# Charger.net
KiCad netlist of a schematic drawn in Altium Designer
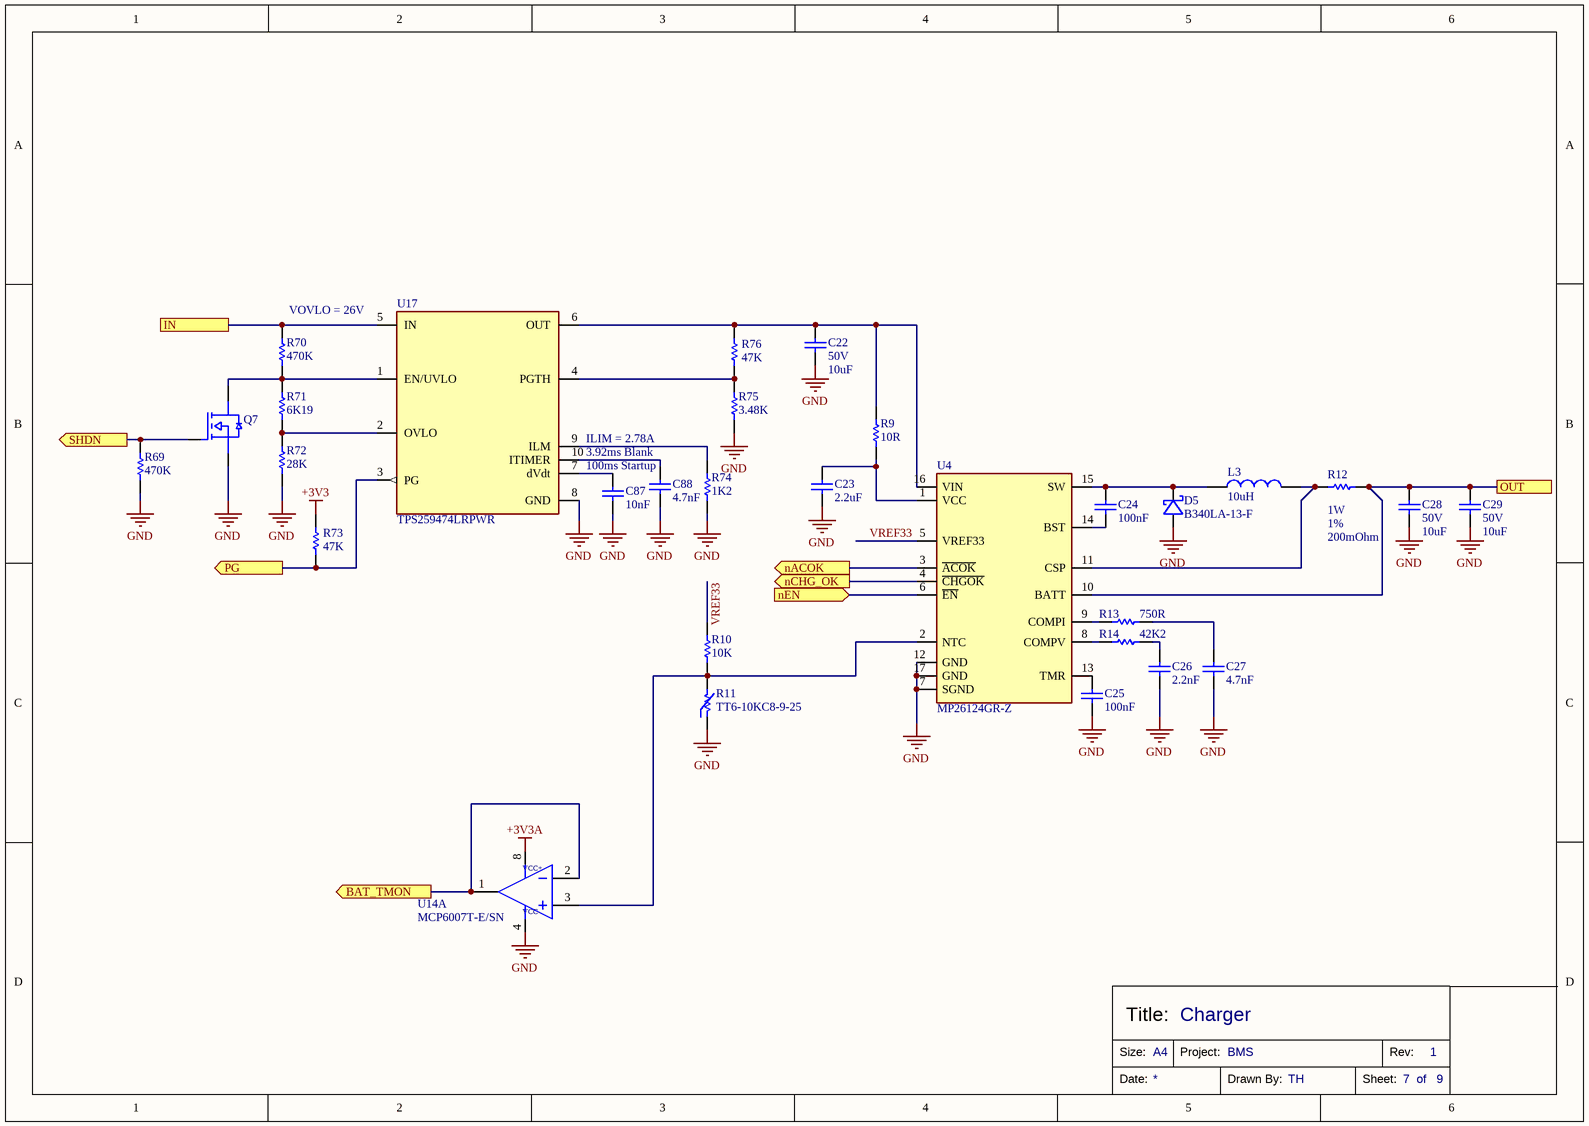
[diagram p0: Charger.SchDoc]

(export (version "E")
  (design (tool "Eeschema 10.0.6"))
  (components
    (comp (ref "C22")
      (value "CL32B106KBJNNNE")
      (footprint "CAPC1210X090")
      (description "10 µF ±10% 50V Ceramic Capacitor X7R 1210 (3225 Metric)")
      (fields
        (field (name "DISTRIBUTOR PART NUMBER") "1276-3387-1-ND")
        (field (name "TOLERANCE") "10%")
        (field (name "VOLTAGE RATING") "50V")
        (field (name "CAPACITANCE") "10uF")
      )
      (libsource (lib "Ahristi_Library") (part "CL32B106KBJNNNE"))
    )
    (comp (ref "C23")
      (value "CL21A225KBFNNNE")
      (footprint "CAPC0805X060")
      (description "2.2uF ±10% 25V Ceramic Capacitor X7R 0805 (2012 Metric)")
      (fields
        (field (name "DISTRIBUTOR PART NUMBER") "1276-6702-1-ND")
        (field (name "TOLERANCE") "10%")
        (field (name "CAPACITANCE") "2.2uF")
      )
      (libsource (lib "Ahristi_Library") (part "CL21A225KBFNNNE"))
    )
    (comp (ref "C24")
      (value "C0603C104K5RACTU")
      (footprint "CAPC0603X040")
      (description "0.1 µF ±10% 50V Ceramic Capacitor X7R 0603 (1608 Metric)")
      (fields
        (field (name "DISTRIBUTOR PART NUMBER") "399-C0603C104K5RACTUCT-ND")
        (field (name "TOLERANCE") "10%")
        (field (name "CAPACITANCE") "100nF")
      )
      (libsource (lib "Ahristi_Library") (part "C0603C104K5RACTU"))
    )
    (comp (ref "C25")
      (value "C0603C104K5RACTU")
      (footprint "CAPC0603X040")
      (description "0.1 µF ±10% 50V Ceramic Capacitor X7R 0603 (1608 Metric)")
      (fields
        (field (name "DISTRIBUTOR PART NUMBER") "399-C0603C104K5RACTUCT-ND")
        (field (name "TOLERANCE") "10%")
        (field (name "CAPACITANCE") "100nF")
      )
      (libsource (lib "Ahristi_Library") (part "C0603C104K5RACTU"))
    )
    (comp (ref "C26")
      (value "CL10B222KB8WPNC")
      (footprint "CAPC0603X060")
      (description "2.2nF ±10% 50V Ceramic Capacitor X7R 0603 (1608 Metric)")
      (fields
        (field (name "DISTRIBUTOR PART NUMBER") "1276-6530-1-ND")
        (field (name "TOLERANCE") "10%")
        (field (name "CAPACITANCE") "2.2nF")
      )
      (libsource (lib "Ahristi_Library") (part "CL10B222KB8WPNC"))
    )
    (comp (ref "C27")
      (value "C0603C472K4RECAUTO")
      (footprint "CAPC0603X040")
      (description "4.7nF ±10% 16V Ceramic Capacitor X7R 0603 (1608 Metric)")
      (fields
        (field (name "TOLERANCE") "10%")
        (field (name "DISTRIBUTOR PART NUMBER") "399-17879-1-ND")
        (field (name "CAPACITANCE") "4.7nF")
      )
      (libsource (lib "Ahristi_Library") (part "C0603C472K4RECAUTO"))
    )
    (comp (ref "C28")
      (value "CL32B106KBJNNNE")
      (footprint "CAPC1210X090")
      (description "10 µF ±10% 50V Ceramic Capacitor X7R 1210 (3225 Metric)")
      (fields
        (field (name "DISTRIBUTOR PART NUMBER") "1276-3387-1-ND")
        (field (name "TOLERANCE") "10%")
        (field (name "VOLTAGE RATING") "50V")
        (field (name "CAPACITANCE") "10uF")
      )
      (libsource (lib "Ahristi_Library") (part "CL32B106KBJNNNE"))
    )
    (comp (ref "C29")
      (value "CL32B106KBJNNNE")
      (footprint "CAPC1210X090")
      (description "10 µF ±10% 50V Ceramic Capacitor X7R 1210 (3225 Metric)")
      (fields
        (field (name "DISTRIBUTOR PART NUMBER") "1276-3387-1-ND")
        (field (name "TOLERANCE") "10%")
        (field (name "VOLTAGE RATING") "50V")
        (field (name "CAPACITANCE") "10uF")
      )
      (libsource (lib "Ahristi_Library") (part "CL32B106KBJNNNE"))
    )
    (comp (ref "C87")
      (value "CL10B103KB8NNNC")
      (footprint "CAPC0603X060")
      (description "10nF ±10% 50V Ceramic Capacitor X7R 0603 (1608 Metric)")
      (fields
        (field (name "DISTRIBUTOR PART NUMBER") "1276-1009-1-ND")
        (field (name "TOLERANCE") "10%")
        (field (name "CAPACITANCE") "10nF")
      )
      (libsource (lib "Ahristi_Library") (part "CL10B103KB8NNNC"))
    )
    (comp (ref "C88")
      (value "C0603C472K4RECAUTO")
      (footprint "CAPC0603X040")
      (description "4.7nF ±10% 16V Ceramic Capacitor X7R 0603 (1608 Metric)")
      (fields
        (field (name "TOLERANCE") "10%")
        (field (name "DISTRIBUTOR PART NUMBER") "399-17879-1-ND")
        (field (name "CAPACITANCE") "4.7nF")
      )
      (libsource (lib "Ahristi_Library") (part "C0603C472K4RECAUTO"))
    )
    (comp (ref "D5")
      (value "B340LA-13-F")
      (footprint "DO-214")
      (description "Diode Schottky 40V 3A 450mV FVf Fast Recovery")
      (fields (field (name "DISTRIBUTOR PART NUMBER") "B340LA-FDICT-ND"))
      (libsource (lib "Ahristi_Library") (part "B340LA-13-F"))
    )
    (comp (ref "L3")
      (value "1274AS-H-100M=P3")
      (footprint "1274AS-H-100M=P3")
      (description "Inductor 10 µH , 4.4 A 30.4mOhm Max Shielded Drum Core")
      (fields (field (name "DISTRIBUTOR PART NUMBER") "490-10846-1-ND") (field (name "INDUCTANCE") "10uH"))
      (libsource (lib "Ahristi_Library") (part "1274AS-H-100M=P3"))
    )
    (comp (ref "Q7")
      (value "T2N7002AK,LM")
      (footprint "SOT23-3 MOSFET")
      (description "N-Channel 60 V 200mA (Ta) 320mW (Ta) Surface Mount SOT-23-3")
      (fields (field (name "DISTRIBUTOR PART NUMBER") "T2N7002AKLMCT-ND"))
      (libsource (lib "Ahristi_Library") (part "T2N7002AK,LM"))
    )
    (comp (ref "R9")
      (value "RMCF0603FT10R0")
      (footprint "RESC0603")
      (description "10 Ohms ±1% 0.1W, 1/10W Chip Resistor 0603 (1608 Metric) Automotive AEC-Q200 Thick Film")
      (fields
        (field (name "TOLERANCE") "1%")
        (field (name "DISTRIBUTOR PART NUMBER") "RMCF0603FT10R0CT-ND")
        (field (name "RESISTANCE") "10R")
      )
      (libsource (lib "Ahristi_Library") (part "RMCF0603FT10R0"))
    )
    (comp (ref "R10")
      (value "RMCF0603FT10K0")
      (footprint "RESC0603")
      (description "10 kOhms ±1% 0.1W, 1/10W Chip Resistor 0603 (1608 Metric) Automotive AEC-Q200 Thick Film")
      (fields
        (field (name "TOLERANCE") "1%")
        (field (name "DISTRIBUTOR PART NUMBER") "RMCF0603FT10K0CT-ND")
        (field (name "RESISTANCE") "10K")
      )
      (libsource (lib "Ahristi_Library") (part "RMCF0603FT10K0"))
    )
    (comp (ref "R11")
      (value "TT6-10KC8-9-25")
      (footprint "TT6-10KC8-9-25")
      (description "NTC Thermistor 10k Probe")
      (fields (field (name "DISTRIBUTOR PART NUMBER") "1912-TT6-10KC8-9-25-ND"))
      (libsource (lib "Ahristi_Library") (part "TT6-10KC8-9-25"))
    )
    (comp (ref "R12")
      (value "WSLT2512R2000FEB")
      (footprint "WSLT2512R2000FEB")
      (fields
        (field (name "DISTRIBUTOR PART NUMBER") "541-10376-1-ND")
        (field (name "POWER") "1W")
        (field (name "TOLERANCE") "1%")
        (field (name "RESISTANCE") "200mOhm")
      )
      (libsource (lib "Ahristi_Library") (part "WSLT2512R2000FEB"))
    )
    (comp (ref "R13")
      (value "RMCF0603FT750R")
      (footprint "RESC0603")
      (description "750 Ohms ±1% 0.1W, 1/10W Chip Resistor 0603 (1608 Metric) Automotive AEC-Q200 Thick Film")
      (fields
        (field (name "TOLERANCE") "1%")
        (field (name "DISTRIBUTOR PART NUMBER") "RMCF0603FT750RCT-ND")
        (field (name "RESISTANCE") "750R")
      )
      (libsource (lib "Ahristi_Library") (part "RMCF0603FT750R"))
    )
    (comp (ref "R14")
      (value "RMCF0603FT42K2")
      (footprint "RESC0603")
      (description "42.2 kOhms ±1% 0.1W, 1/10W Chip Resistor 0603 (1608 Metric) Automotive AEC-Q200 Thick Film")
      (fields
        (field (name "TOLERANCE") "1%")
        (field (name "DISTRIBUTOR PART NUMBER") "RMCF0603FT42K2CT-ND")
        (field (name "RESISTANCE") "42K2")
      )
      (libsource (lib "Ahristi_Library") (part "RMCF0603FT42K2"))
    )
    (comp (ref "R69")
      (value "RMCF0603FT470K")
      (footprint "RESC0603")
      (description "470 kOhms ±1% 0.1W, 1/10W Chip Resistor 0603 (1608 Metric) Automotive AEC-Q200 Thick Film")
      (fields
        (field (name "TOLERANCE") "1%")
        (field (name "DISTRIBUTOR PART NUMBER") "RMCF0603FT470KCT-ND")
        (field (name "RESISTANCE") "470K")
      )
      (libsource (lib "Ahristi_Library") (part "RMCF0603FT470K"))
    )
    (comp (ref "R70")
      (value "RMCF0603FT470K")
      (footprint "RESC0603")
      (description "470 kOhms ±1% 0.1W, 1/10W Chip Resistor 0603 (1608 Metric) Automotive AEC-Q200 Thick Film")
      (fields
        (field (name "TOLERANCE") "1%")
        (field (name "DISTRIBUTOR PART NUMBER") "RMCF0603FT470KCT-ND")
        (field (name "RESISTANCE") "470K")
      )
      (libsource (lib "Ahristi_Library") (part "RMCF0603FT470K"))
    )
    (comp (ref "R71")
      (value "RMCF0603FT6K19")
      (footprint "RESC0603")
      (description "6.19 kOhms ±1% 0.1W, 1/10W Chip Resistor 0603 (1608 Metric) Automotive AEC-Q200 Thick Film")
      (fields
        (field (name "TOLERANCE") "1%")
        (field (name "DISTRIBUTOR PART NUMBER") "RMCF0603FT6K19CT-ND")
        (field (name "RESISTANCE") "6K19")
      )
      (libsource (lib "Ahristi_Library") (part "RMCF0603FT6K19"))
    )
    (comp (ref "R72")
      (value "RMCF0603FT28K0")
      (footprint "RESC0603")
      (description "28 kOhms ±1% 0.1W, 1/10W Chip Resistor 0603 (1608 Metric) Automotive AEC-Q200 Thick Film")
      (fields
        (field (name "TOLERANCE") "1%")
        (field (name "DISTRIBUTOR PART NUMBER") "RMCF0603FT28K0CT-ND")
        (field (name "RESISTANCE") "28K")
      )
      (libsource (lib "Ahristi_Library") (part "RMCF0603FT28K0"))
    )
    (comp (ref "R73")
      (value "RMCF0603FT47K0")
      (footprint "RESC0603")
      (description "47 kOhms ±1% 0.1W, 1/10W Chip Resistor 0603 (1608 Metric) Automotive AEC-Q200 Thick Film")
      (fields
        (field (name "TOLERANCE") "1%")
        (field (name "DISTRIBUTOR PART NUMBER") "RMCF0603FT47K0CT-ND")
        (field (name "RESISTANCE") "47K")
      )
      (libsource (lib "Ahristi_Library") (part "RMCF0603FT47K0"))
    )
    (comp (ref "R74")
      (value "RMCF0603FT1K2")
      (footprint "RESC0603")
      (description "1.2 kOhms ±1% 0.1W, 1/10W Chip Resistor 0603 (1608 Metric) Automotive AEC-Q200 Thick Film")
      (fields
        (field (name "TOLERANCE") "1%")
        (field (name "DISTRIBUTOR PART NUMBER") "RMCF0603FT1K20CT-ND")
        (field (name "RESISTANCE") "1K2")
      )
      (libsource (lib "Ahristi_Library") (part "RMCF0603FT1K2"))
    )
    (comp (ref "R75")
      (value "RMCF0603FT3K48")
      (footprint "RESC0603")
      (description "3.48 kOhms ±1% 0.1W, 1/10W Chip Resistor 0603 (1608 Metric) Automotive AEC-Q200 Thick Film")
      (fields
        (field (name "TOLERANCE") "1%")
        (field (name "DISTRIBUTOR PART NUMBER") "RMCF0603FT3K48CT-ND")
        (field (name "RESISTANCE") "3.48K")
      )
      (libsource (lib "Ahristi_Library") (part "RMCF0603FT3K48"))
    )
    (comp (ref "R76")
      (value "RMCF0603FT47K0")
      (footprint "RESC0603")
      (description "47 kOhms ±1% 0.1W, 1/10W Chip Resistor 0603 (1608 Metric) Automotive AEC-Q200 Thick Film")
      (fields
        (field (name "TOLERANCE") "1%")
        (field (name "DISTRIBUTOR PART NUMBER") "RMCF0603FT47K0CT-ND")
        (field (name "RESISTANCE") "47K")
      )
      (libsource (lib "Ahristi_Library") (part "RMCF0603FT47K0"))
    )
    (comp (ref "U4")
      (value "MP26124GR-Z")
      (footprint "qfn-16")
      (description "Charger IC Lithium Ion 24V Input, 2A, 600kHz, 4S Cell Switching")
      (fields (field (name "DISTRIBUTOR PART NUMBER") "1589-1993-1-ND"))
      (libsource (lib "Ahristi_Library") (part "MP26124GR-Z"))
    )
    (comp (ref "U14")
      (value "MCP6007T-E/SN")
      (footprint "SOIC-8")
      (description "Operational Amplifier general purpose, 2-Circuit 1.8V ~ 5.5V 1MHz")
      (fields (field (name "DISTRIBUTOR PART NUMBER") "150-MCP6007T-E/SNCT-ND"))
      (libsource (lib "Ahristi_Library") (part "MCP6007T-E/SN"))
    )
    (comp (ref "U17")
      (value "TPS259474LRPWR")
      (footprint "VFQFN-10")
      (description "eFuse 5.5A, 2.7V~23V, 28mOhm, Reverse Current Blocking with Input Reverse Polarity Protection")
      (fields (field (name "DISTRIBUTOR PART NUMBER") "296-TPS259474LRPWRCT-ND"))
      (libsource (lib "Ahristi_Library") (part "TPS259474LRPWR"))
    )
  )
  (nets
    (net (code "1") (name "+3V3") (class "Default")
      (node (ref "R73") (pin "2") (pinfunction "2_2") (pintype "passive"))
    )
    (net (code "2") (name "+3V3A") (class "Default")
      (node (ref "U14") (pin "8") (pinfunction "VCC+_8") (pintype "passive"))
    )
    (net (code "3") (name "/BAT_TMON") (class "Default")
      (node (ref "U14") (pin "1") (pinfunction "OUTA_1") (pintype "passive"))
      (node (ref "U14") (pin "2") (pinfunction "INA-_2") (pintype "passive"))
    )
    (net (code "4") (name "/IN") (class "Default")
      (node (ref "R70") (pin "2") (pinfunction "2_2") (pintype "passive"))
      (node (ref "U17") (pin "5") (pinfunction "IN_5") (pintype "passive"))
    )
    (net (code "5") (name "/OUT") (class "Default")
      (node (ref "C28") (pin "2") (pinfunction "2_2") (pintype "passive"))
      (node (ref "C29") (pin "2") (pinfunction "2_2") (pintype "passive"))
      (node (ref "R12") (pin "2") (pinfunction "2_2") (pintype "passive"))
      (node (ref "U4") (pin "10") (pinfunction "BATT_10") (pintype "passive"))
    )
    (net (code "6") (name "/PG") (class "Default")
      (node (ref "R73") (pin "1") (pinfunction "1_1") (pintype "passive"))
      (node (ref "U17") (pin "3") (pinfunction "PG_3") (pintype "output"))
    )
    (net (code "7") (name "/SHDN") (class "Default")
      (node (ref "Q7") (pin "G") (pinfunction "G_G") (pintype "passive"))
      (node (ref "R69") (pin "2") (pinfunction "2_2") (pintype "passive"))
    )
    (net (code "8") (name "/VREF33") (class "Default")
      (node (ref "R10") (pin "2") (pinfunction "2_2") (pintype "passive"))
      (node (ref "U4") (pin "5") (pinfunction "VREF33_5") (pintype "passive"))
    )
    (net (code "9") (name "/nACOK") (class "Default")
      (node (ref "U4") (pin "3") (pinfunction "~{ACOK}_3") (pintype "passive"))
    )
    (net (code "10") (name "/nCHG_OK") (class "Default")
      (node (ref "U4") (pin "4") (pinfunction "~{CHGOK}_4") (pintype "passive"))
    )
    (net (code "11") (name "/nEN") (class "Default")
      (node (ref "U4") (pin "6") (pinfunction "~{EN}_6") (pintype "passive"))
    )
    (net (code "12") (name "GND") (class "Default")
      (node (ref "C22") (pin "1") (pinfunction "1_1") (pintype "passive"))
      (node (ref "C23") (pin "1") (pinfunction "1_1") (pintype "passive"))
      (node (ref "C25") (pin "1") (pinfunction "1_1") (pintype "passive"))
      (node (ref "C26") (pin "1") (pinfunction "1_1") (pintype "passive"))
      (node (ref "C27") (pin "1") (pinfunction "1_1") (pintype "passive"))
      (node (ref "C28") (pin "1") (pinfunction "1_1") (pintype "passive"))
      (node (ref "C29") (pin "1") (pinfunction "1_1") (pintype "passive"))
      (node (ref "C87") (pin "2") (pinfunction "2_2") (pintype "passive"))
      (node (ref "C88") (pin "2") (pinfunction "2_2") (pintype "passive"))
      (node (ref "D5") (pin "A") (pinfunction "A_A") (pintype "passive"))
      (node (ref "Q7") (pin "S") (pinfunction "S_S") (pintype "passive"))
      (node (ref "R11") (pin "1") (pinfunction "1_1") (pintype "passive"))
      (node (ref "R69") (pin "1") (pinfunction "1_1") (pintype "passive"))
      (node (ref "R72") (pin "1") (pinfunction "1_1") (pintype "passive"))
      (node (ref "R74") (pin "1") (pinfunction "1_1") (pintype "passive"))
      (node (ref "R75") (pin "1") (pinfunction "1_1") (pintype "passive"))
      (node (ref "U14") (pin "4") (pinfunction "VCC-_4") (pintype "passive"))
      (node (ref "U17") (pin "8") (pinfunction "GND_8") (pintype "passive"))
      (node (ref "U4") (pin "12") (pinfunction "GND_12") (pintype "passive"))
      (node (ref "U4") (pin "17") (pinfunction "GND_17") (pintype "passive"))
      (node (ref "U4") (pin "7") (pinfunction "SGND_7") (pintype "passive"))
    )
    (net (code "13") (name "Net-(C26-Pad2)") (class "Default")
      (node (ref "C26") (pin "2") (pinfunction "2_2") (pintype "passive"))
      (node (ref "R14") (pin "1") (pinfunction "1_1") (pintype "passive"))
    )
    (net (code "14") (name "Net-(C27-Pad2)") (class "Default")
      (node (ref "C27") (pin "2") (pinfunction "2_2") (pintype "passive"))
      (node (ref "R13") (pin "2") (pinfunction "2_2") (pintype "passive"))
    )
    (net (code "15") (name "Net-(U4-BST)") (class "Default")
      (node (ref "C24") (pin "1") (pinfunction "1_1") (pintype "passive"))
      (node (ref "U4") (pin "14") (pinfunction "BST_14") (pintype "passive"))
    )
    (net (code "16") (name "Net-(U4-COMPI)") (class "Default")
      (node (ref "R13") (pin "1") (pinfunction "1_1") (pintype "passive"))
      (node (ref "U4") (pin "9") (pinfunction "COMPI_9") (pintype "passive"))
    )
    (net (code "17") (name "Net-(U4-COMPV)") (class "Default")
      (node (ref "R14") (pin "2") (pinfunction "2_2") (pintype "passive"))
      (node (ref "U4") (pin "8") (pinfunction "COMPV_8") (pintype "passive"))
    )
    (net (code "18") (name "Net-(U4-CSP)") (class "Default")
      (node (ref "L3") (pin "2") (pinfunction "2_2") (pintype "passive"))
      (node (ref "R12") (pin "1") (pinfunction "1_1") (pintype "passive"))
      (node (ref "U4") (pin "11") (pinfunction "CSP_11") (pintype "passive"))
    )
    (net (code "19") (name "Net-(U4-SW)") (class "Default")
      (node (ref "C24") (pin "2") (pinfunction "2_2") (pintype "passive"))
      (node (ref "D5") (pin "K") (pinfunction "K_K") (pintype "passive"))
      (node (ref "L3") (pin "1") (pinfunction "1_1") (pintype "passive"))
      (node (ref "U4") (pin "15") (pinfunction "SW_15") (pintype "passive"))
    )
    (net (code "20") (name "Net-(U4-TMR)") (class "Default")
      (node (ref "C25") (pin "2") (pinfunction "2_2") (pintype "passive"))
      (node (ref "U4") (pin "13") (pinfunction "TMR_13") (pintype "passive"))
    )
    (net (code "21") (name "Net-(U4-VCC)") (class "Default")
      (node (ref "C23") (pin "2") (pinfunction "2_2") (pintype "passive"))
      (node (ref "R9") (pin "1") (pinfunction "1_1") (pintype "passive"))
      (node (ref "U4") (pin "1") (pinfunction "VCC_1") (pintype "passive"))
    )
    (net (code "22") (name "Net-(U14A-INA+)") (class "Default")
      (node (ref "R10") (pin "1") (pinfunction "1_1") (pintype "passive"))
      (node (ref "R11") (pin "2") (pinfunction "2_2") (pintype "passive"))
      (node (ref "U14") (pin "3") (pinfunction "INA+_3") (pintype "passive"))
      (node (ref "U4") (pin "2") (pinfunction "NTC_2") (pintype "passive"))
    )
    (net (code "23") (name "Net-(U17-EN{slash}UVLO)") (class "Default")
      (node (ref "Q7") (pin "D") (pinfunction "D_D") (pintype "passive"))
      (node (ref "R70") (pin "1") (pinfunction "1_1") (pintype "passive"))
      (node (ref "R71") (pin "2") (pinfunction "2_2") (pintype "passive"))
      (node (ref "U17") (pin "1") (pinfunction "EN/UVLO_1") (pintype "passive"))
    )
    (net (code "24") (name "Net-(U17-ILM)") (class "Default")
      (node (ref "R74") (pin "2") (pinfunction "2_2") (pintype "passive"))
      (node (ref "U17") (pin "9") (pinfunction "ILM_9") (pintype "passive"))
    )
    (net (code "25") (name "Net-(U17-ITIMER)") (class "Default")
      (node (ref "C88") (pin "1") (pinfunction "1_1") (pintype "passive"))
      (node (ref "U17") (pin "10") (pinfunction "ITIMER_10") (pintype "passive"))
    )
    (net (code "26") (name "Net-(U17-OUT)") (class "Default")
      (node (ref "C22") (pin "2") (pinfunction "2_2") (pintype "passive"))
      (node (ref "R76") (pin "2") (pinfunction "2_2") (pintype "passive"))
      (node (ref "R9") (pin "2") (pinfunction "2_2") (pintype "passive"))
      (node (ref "U17") (pin "6") (pinfunction "OUT_6") (pintype "passive"))
      (node (ref "U4") (pin "16") (pinfunction "VIN_16") (pintype "passive"))
    )
    (net (code "27") (name "Net-(U17-OVLO)") (class "Default")
      (node (ref "R71") (pin "1") (pinfunction "1_1") (pintype "passive"))
      (node (ref "R72") (pin "2") (pinfunction "2_2") (pintype "passive"))
      (node (ref "U17") (pin "2") (pinfunction "OVLO_2") (pintype "passive"))
    )
    (net (code "28") (name "Net-(U17-PGTH)") (class "Default")
      (node (ref "R75") (pin "2") (pinfunction "2_2") (pintype "passive"))
      (node (ref "R76") (pin "1") (pinfunction "1_1") (pintype "passive"))
      (node (ref "U17") (pin "4") (pinfunction "PGTH_4") (pintype "passive"))
    )
    (net (code "29") (name "Net-(U17-dVdt)") (class "Default")
      (node (ref "C87") (pin "1") (pinfunction "1_1") (pintype "passive"))
      (node (ref "U17") (pin "7") (pinfunction "dVdt_7") (pintype "passive"))
    )
  )
)
